# Sheet2.net
KiCad netlist of a schematic drawn in Altium Designer
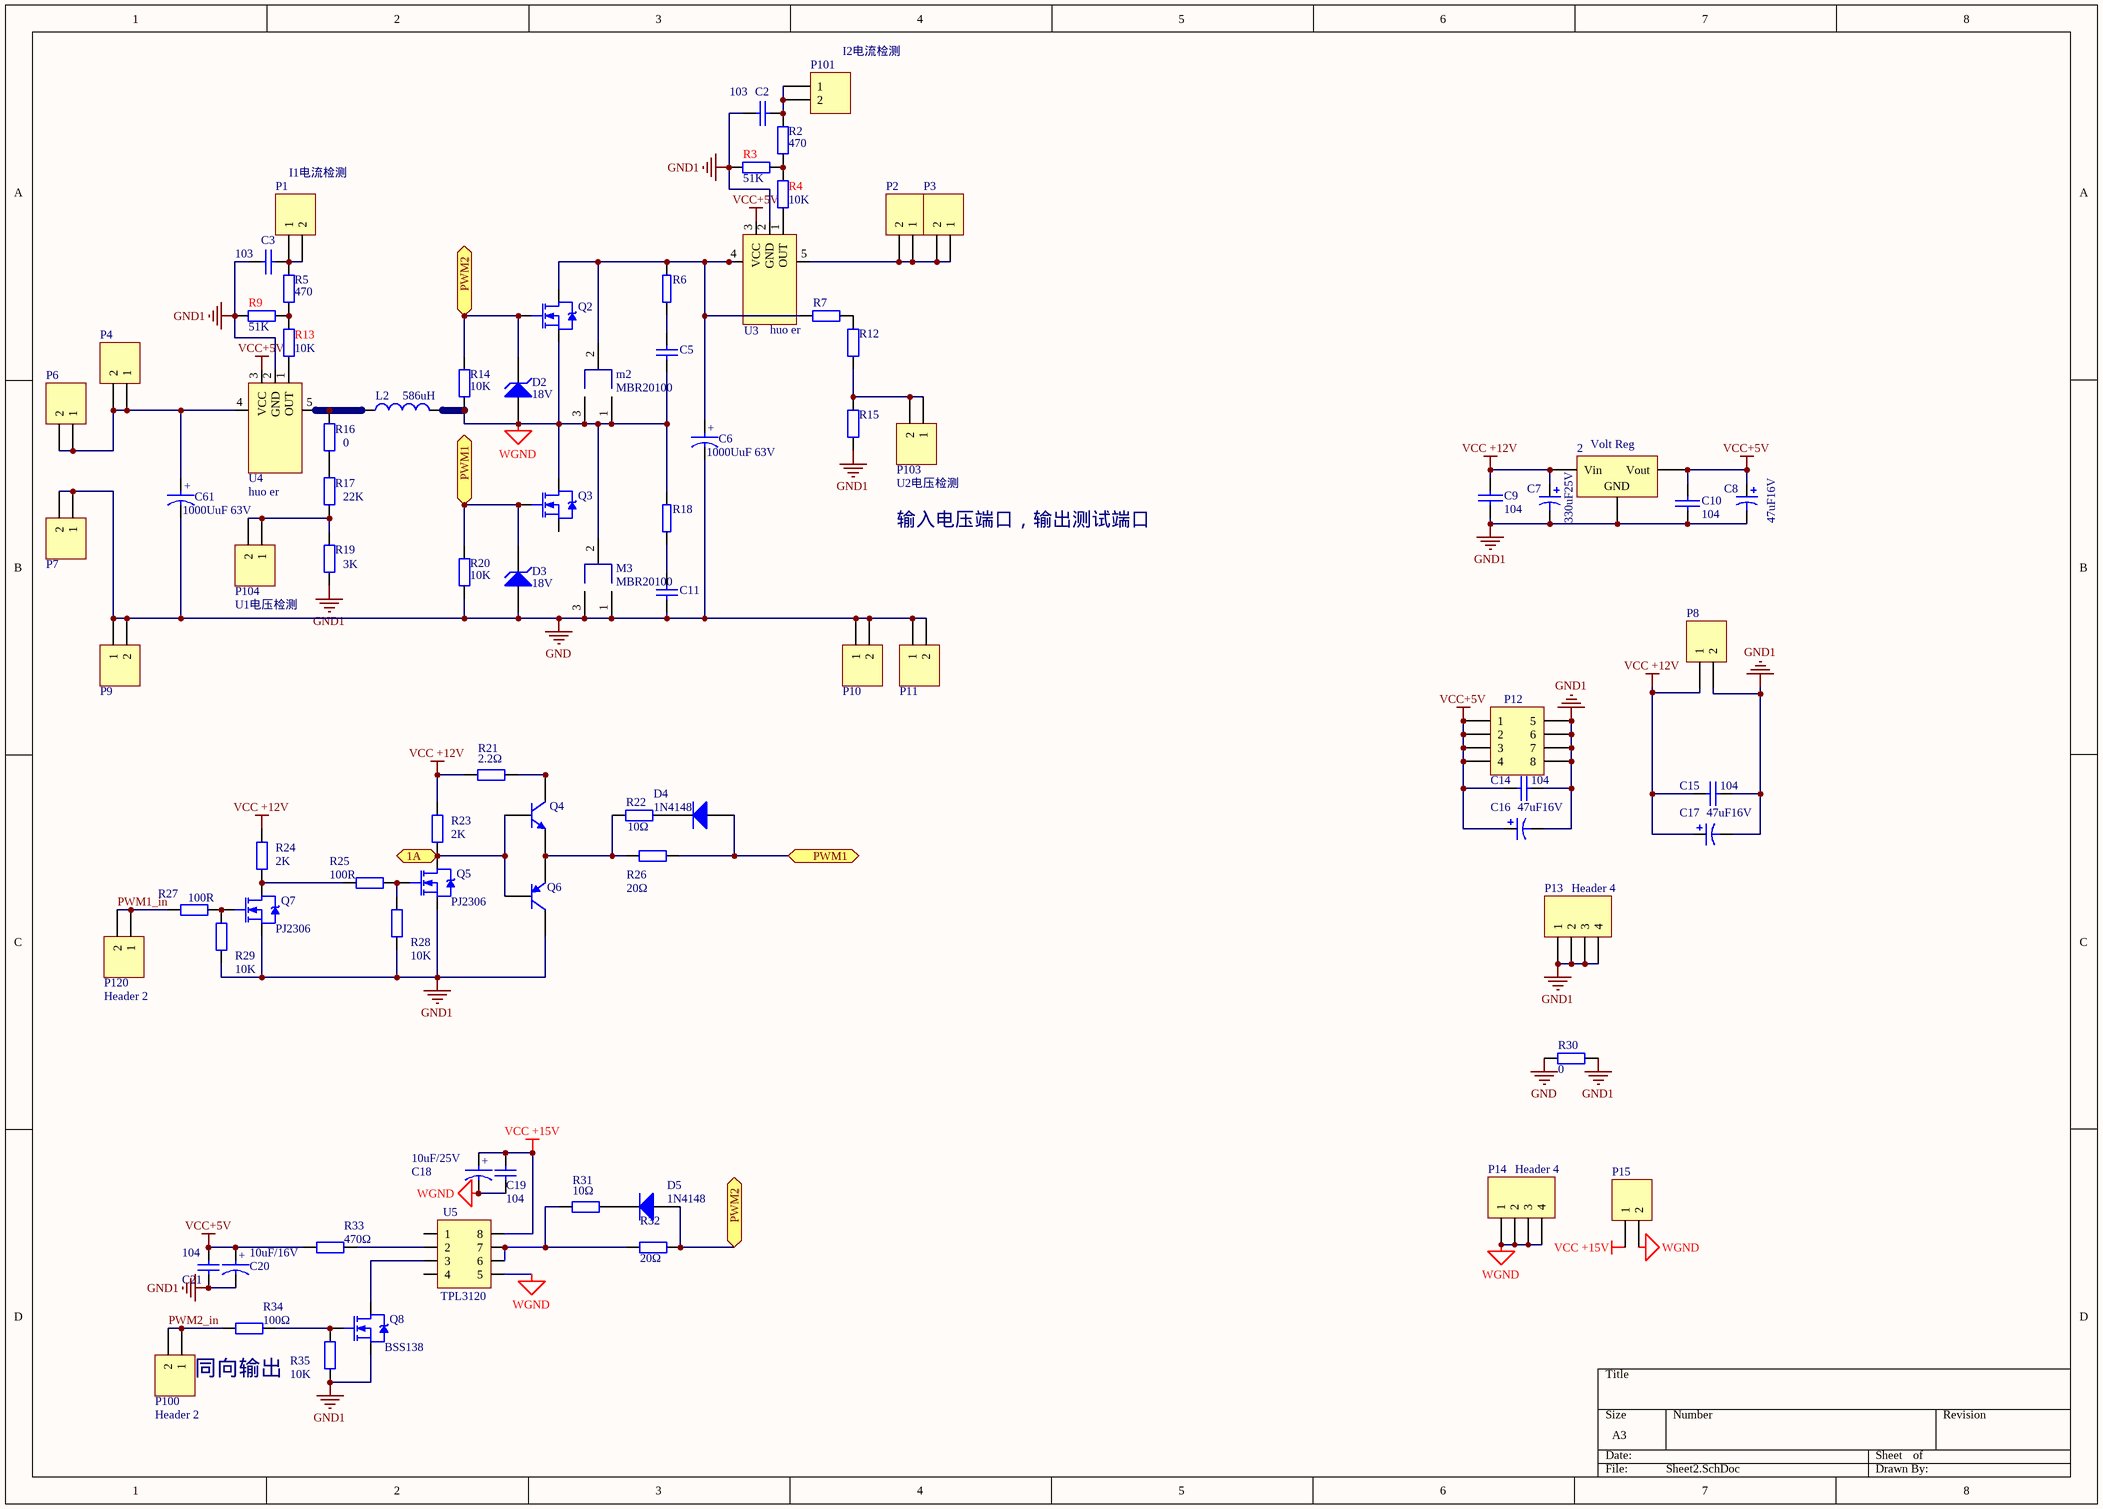
[diagram p0: Sheet2.SchDoc]

(export (version "E")
  (design (tool "Eeschema 10.0.6"))
  (components
    (comp (ref "2")
      (value "Volt Reg")
      (footprint "7812")
      (description "Voltage Regulator")
      (fields (field (name "PUBLISHER") "Altium Limited"))
      (libsource (lib "Miscellaneous Devices") (part "Volt Reg"))
    )
    (comp (ref "C2")
      (value "103")
      (footprint "C0805")
      (description "Capacitor")
      (libsource (lib "*") (part "CAP"))
    )
    (comp (ref "C3")
      (value "103")
      (footprint "C0805")
      (description "Capacitor")
      (libsource (lib "*") (part "CAP"))
    )
    (comp (ref "C5")
      (value "681")
      (footprint "接线端子")
      (description "Capacitor")
      (fields
        (field (name "MANUFACTURER") "Generic Components")
        (field (name "PUBLISHER") "Altium Hobart Technology Centre")
      )
      (libsource (lib "Miscellaneous Devices") (part "Cap"))
    )
    (comp (ref "C6")
      (value "1000UuF 63V")
      (footprint "RB.4/.8")
      (description "Capacitor")
      (libsource (lib "*") (part "CAPACITOR POL"))
    )
    (comp (ref "C7")
      (value "330uF25V")
      (footprint "RB.2/.4_1")
      (description "Polarized Capacitor (Radial)")
      (fields (field (name "PUBLISHER") "Altium Limited"))
      (libsource (lib "Miscellaneous Devices") (part "Cap Pol1"))
    )
    (comp (ref "C8")
      (value "47uF16V")
      (footprint "RB.1/.2")
      (description "Polarized Capacitor (Radial)")
      (fields (field (name "PUBLISHER") "Altium Limited"))
      (libsource (lib "Miscellaneous Devices") (part "Cap Pol1"))
    )
    (comp (ref "C9")
      (value "104")
      (footprint "C0805")
      (description "Capacitor")
      (libsource (lib "*") (part "CAP"))
    )
    (comp (ref "C10")
      (value "104")
      (footprint "C0805")
      (description "Capacitor")
      (libsource (lib "*") (part "CAP"))
    )
    (comp (ref "C11")
      (value "681")
      (footprint "接线端子")
      (description "Capacitor")
      (fields
        (field (name "MANUFACTURER") "Generic Components")
        (field (name "PUBLISHER") "Altium Hobart Technology Centre")
      )
      (libsource (lib "Miscellaneous Devices") (part "Cap"))
    )
    (comp (ref "C14")
      (value "104")
      (footprint "C0805")
      (description "Capacitor")
      (libsource (lib "*") (part "CAP"))
    )
    (comp (ref "C15")
      (value "104")
      (footprint "C0805")
      (description "Capacitor")
      (libsource (lib "*") (part "CAP"))
    )
    (comp (ref "C16")
      (value "47uF16V")
      (footprint "RB.1/.2")
      (description "Polarized Capacitor (Radial)")
      (fields (field (name "PUBLISHER") "Altium Limited"))
      (libsource (lib "Miscellaneous Devices") (part "Cap Pol1"))
    )
    (comp (ref "C17")
      (value "47uF16V")
      (footprint "RB.1/.2")
      (description "Polarized Capacitor (Radial)")
      (fields (field (name "PUBLISHER") "Altium Limited"))
      (libsource (lib "Miscellaneous Devices") (part "Cap Pol1"))
    )
    (comp (ref "C18")
      (value "10uF/25V")
      (footprint "RB.1/.2")
      (description "Capacitor")
      (libsource (lib "*") (part "CAPACITOR POL"))
    )
    (comp (ref "C19")
      (value "104")
      (footprint "C0805")
      (description "Capacitor")
      (fields
        (field (name "MANUFACTURER") "Generic Components")
        (field (name "PUBLISHER") "Altium Hobart Technology Centre")
      )
      (libsource (lib "Miscellaneous Devices") (part "Cap"))
    )
    (comp (ref "C20")
      (value "10uF/16V")
      (footprint "RB.1/.2")
      (description "Capacitor")
      (libsource (lib "*") (part "CAPACITOR POL"))
    )
    (comp (ref "C21")
      (value "104")
      (footprint "C0805")
      (description "Capacitor")
      (fields
        (field (name "MANUFACTURER") "Generic Components")
        (field (name "PUBLISHER") "Altium Hobart Technology Centre")
      )
      (libsource (lib "Miscellaneous Devices") (part "Cap"))
    )
    (comp (ref "C61")
      (value "1000UuF 63V")
      (footprint "RB.4/.8")
      (description "Capacitor")
      (libsource (lib "*") (part "CAPACITOR POL"))
    )
    (comp (ref "D2")
      (value "D Zener")
      (footprint "DIODE0.4_ZD")
      (description "Zener Diode")
      (fields
        (field (name "MANUFACTURER") "Generic Components")
        (field (name "SUBCLASS") "18V")
        (field (name "PUBLISHER") "Altium Hobart Technology Centre")
      )
      (libsource (lib "Miscellaneous Devices") (part "D Zener"))
    )
    (comp (ref "D3")
      (value "D Zener")
      (footprint "DIODE0.4_ZD")
      (description "Zener Diode")
      (fields
        (field (name "MANUFACTURER") "Generic Components")
        (field (name "SUBCLASS") "18V")
        (field (name "PUBLISHER") "Altium Hobart Technology Centre")
      )
      (libsource (lib "Miscellaneous Devices") (part "D Zener"))
    )
    (comp (ref "D4")
      (value "1N4148")
      (footprint "1206d")
      (description "Default Diode")
      (fields
        (field (name "MANUFACTURER") "Generic Components")
        (field (name "PUBLISHER") "Altium Hobart Technology Centre")
      )
      (libsource (lib "Miscellaneous Devices") (part "Diode"))
    )
    (comp (ref "D5")
      (value "1N4148")
      (footprint "1206d")
      (description "Default Diode")
      (fields
        (field (name "MANUFACTURER") "Generic Components")
        (field (name "PUBLISHER") "Altium Hobart Technology Centre")
      )
      (libsource (lib "Miscellaneous Devices") (part "Diode"))
    )
    (comp (ref "L2")
      (value "586uH")
      (footprint "130060")
      (description "Inductor")
      (fields (field (name "Comment") "12uH") (field (name "PUBLISHER") "Altium Limited"))
      (libsource (lib "older_ad09原理图") (part "Inductor_2"))
    )
    (comp (ref "m2") (value "MBR20100") (footprint "SFM-T3/A4.7V") (libsource (lib "Schlib1") (part "20010")))
    (comp (ref "M3") (value "MBR20100") (footprint "SFM-T3/A4.7V") (libsource (lib "Schlib1") (part "20010")))
    (comp (ref "P1")
      (value "I1电流检测")
      (footprint "HDR1X2")
      (description "Header, 2-Pin")
      (fields (field (name "PUBLISHER") "Altium Limited"))
      (libsource (lib "") (part "Header 2_2"))
    )
    (comp (ref "P2")
      (value "Header 2")
      (footprint "冷压插头")
      (description "Header, 2-Pin")
      (fields (field (name "PUBLISHER") "Altium Limited"))
      (libsource (lib "") (part "Header 2_1"))
    )
    (comp (ref "P3")
      (value "Header 2")
      (footprint "冷压插头")
      (description "Header, 2-Pin")
      (fields (field (name "PUBLISHER") "Altium Limited"))
      (libsource (lib "") (part "Header 2_1"))
    )
    (comp (ref "P4")
      (value "Header 2")
      (footprint "冷压插头")
      (description "Header, 2-Pin")
      (fields (field (name "PUBLISHER") "Altium Limited"))
      (libsource (lib "") (part "Header 2_1"))
    )
    (comp (ref "P6")
      (value "Header 2")
      (footprint "冷压插头")
      (description "Header, 2-Pin")
      (fields (field (name "PUBLISHER") "Altium Limited"))
      (libsource (lib "") (part "Header 2_1"))
    )
    (comp (ref "P7")
      (value "Header 2")
      (footprint "冷压插头")
      (description "Header, 2-Pin")
      (fields (field (name "PUBLISHER") "Altium Limited"))
      (libsource (lib "Miscellaneous Connectors") (part "Header 2"))
    )
    (comp (ref "P8")
      (value "Header 2")
      (footprint "SIP2_B")
      (description "Header, 2-Pin")
      (fields (field (name "PUBLISHER") "Altium Limited"))
      (libsource (lib "") (part "Header 2_2"))
    )
    (comp (ref "P9")
      (value "Header 2")
      (footprint "冷压插头")
      (description "Header, 2-Pin")
      (fields (field (name "PUBLISHER") "Altium Limited"))
      (libsource (lib "") (part "Header 2_3"))
    )
    (comp (ref "P10")
      (value "Header 2")
      (footprint "冷压插头")
      (description "Header, 2-Pin")
      (fields (field (name "PUBLISHER") "Altium Limited"))
      (libsource (lib "") (part "Header 2_3"))
    )
    (comp (ref "P11")
      (value "Header 2")
      (footprint "冷压插头")
      (description "Header, 2-Pin")
      (fields (field (name "PUBLISHER") "Altium Limited"))
      (libsource (lib "") (part "Header 2_3"))
    )
    (comp (ref "P12")
      (value "~")
      (footprint "HDR2X4_CEN")
      (description "Header, 4-Pin, Dual row")
      (fields (field (name "PUBLISHER") "Altium Limited"))
      (libsource (lib "Miscellaneous Connectors") (part "Header 4X2A"))
    )
    (comp (ref "P13")
      (value "Header 4")
      (footprint "HDR1X4")
      (description "Header, 4-Pin")
      (fields (field (name "PUBLISHER") "Altium Limited"))
      (libsource (lib "Miscellaneous Connectors") (part "Header 4"))
    )
    (comp (ref "P14")
      (value "Header 4")
      (footprint "HDR1X4")
      (description "Header, 4-Pin")
      (fields (field (name "PUBLISHER") "Altium Limited"))
      (libsource (lib "Miscellaneous Connectors") (part "Header 4"))
    )
    (comp (ref "P15")
      (value "Header 2")
      (footprint "SIP2_B")
      (description "Header, 2-Pin")
      (fields (field (name "PUBLISHER") "Altium Limited"))
      (libsource (lib "") (part "Header 2_2"))
    )
    (comp (ref "P100")
      (value "Header 2")
      (footprint "HDR1X2")
      (description "Header, 2-Pin")
      (fields (field (name "PUBLISHER") "Altium Limited"))
      (libsource (lib "Miscellaneous Connectors") (part "Header 2"))
    )
    (comp (ref "P101")
      (value "I2电流检测")
      (footprint "HDR1X2")
      (description "Header, 2-Pin")
      (fields (field (name "PUBLISHER") "Altium Limited"))
      (libsource (lib "") (part "Header 2_4"))
    )
    (comp (ref "P103")
      (value "U2电压检测")
      (footprint "HDR1X2")
      (description "Header, 2-Pin")
      (fields (field (name "PUBLISHER") "Altium Limited"))
      (libsource (lib "Miscellaneous Connectors") (part "Header 2"))
    )
    (comp (ref "P104")
      (value "U1电压检测")
      (footprint "HDR1X2")
      (description "Header, 2-Pin")
      (fields (field (name "PUBLISHER") "Altium Limited"))
      (libsource (lib "Miscellaneous Connectors") (part "Header 2"))
    )
    (comp (ref "P120")
      (value "Header 2")
      (footprint "HDR1X2")
      (description "Header, 2-Pin")
      (fields (field (name "PUBLISHER") "Altium Limited"))
      (libsource (lib "Miscellaneous Connectors") (part "Header 2"))
    )
    (comp (ref "Q2")
      (value "IRF830")
      (footprint "SFM-T3/A4.7V")
      (description "CQ-IRF840")
      (libsource (lib "*") (part "IRF840"))
    )
    (comp (ref "Q3")
      (value "IRF830")
      (footprint "SFM-T3/A4.7V")
      (description "CQ-IRF840")
      (libsource (lib "*") (part "IRF840"))
    )
    (comp (ref "Q4")
      (value "8050")
      (footprint "TO-92")
      (description "NPN General Purpose Amplifier")
      (fields
        (field (name "MANUFACTURER") "Generic Components")
        (field (name "PUBLISHER") "Altium Hobart Technology Centre")
      )
      (libsource (lib "Miscellaneous Devices") (part "2N3904"))
    )
    (comp (ref "Q5")
      (value "PJ2306")
      (footprint "sot-23")
      (description "CQ-IRF840")
      (libsource (lib "") (part "IRF840_1"))
    )
    (comp (ref "Q6")
      (value "8550")
      (footprint "TO-92")
      (description "PNP Bipolar Transistor")
      (fields
        (field (name "MANUFACTURER") "Generic Components")
        (field (name "PUBLISHER") "Altium Hobart Technology Centre")
      )
      (libsource (lib "Miscellaneous Devices") (part "PNP"))
    )
    (comp (ref "Q7")
      (value "PJ2306")
      (footprint "sot-23")
      (description "CQ-IRF840")
      (libsource (lib "") (part "IRF840_1"))
    )
    (comp (ref "Q8")
      (value "BSS138")
      (footprint "sot-23")
      (description "CQ-IRF840")
      (libsource (lib "") (part "IRF840_1"))
    )
    (comp (ref "R2")
      (value "470")
      (footprint "R0805")
      (description "Resistor")
      (fields
        (field (name "MANUFACTURER") "Generic Components")
        (field (name "Comment") "Res2")
        (field (name "PUBLISHER") "Altium Hobart Technology Centre")
      )
      (libsource (lib "") (part "Res2_1"))
    )
    (comp (ref "R3")
      (value "51K")
      (footprint "R0805")
      (description "Resistor")
      (fields (field (name "PUBLISHER") "Altium Limited"))
      (libsource (lib "") (part "Res2_2"))
    )
    (comp (ref "R4")
      (value "10K")
      (footprint "R0805")
      (description "Resistor")
      (fields (field (name "PUBLISHER") "Altium Limited"))
      (libsource (lib "") (part "Res2_3"))
    )
    (comp (ref "R5")
      (value "470")
      (footprint "R0805")
      (description "Resistor")
      (fields
        (field (name "MANUFACTURER") "Generic Components")
        (field (name "Comment") "Res2")
        (field (name "PUBLISHER") "Altium Hobart Technology Centre")
      )
      (libsource (lib "") (part "Res2_1"))
    )
    (comp (ref "R6") (value "20Ω/2W") (footprint "S-R2W") (libsource (lib "*") (part "R")))
    (comp (ref "R7")
      (value "Res2")
      (footprint "R0805")
      (description "Resistor")
      (fields
        (field (name "MANUFACTURER") "Generic Components")
        (field (name "PUBLISHER") "Altium Hobart Technology Centre")
      )
      (libsource (lib "Miscellaneous Devices") (part "Res2"))
    )
    (comp (ref "R9")
      (value "51K")
      (footprint "R0805")
      (description "Resistor")
      (fields (field (name "PUBLISHER") "Altium Limited"))
      (libsource (lib "") (part "Res2_2"))
    )
    (comp (ref "R12")
      (value "Res2")
      (footprint "R0805")
      (description "Resistor")
      (fields
        (field (name "MANUFACTURER") "Generic Components")
        (field (name "PUBLISHER") "Altium Hobart Technology Centre")
      )
      (libsource (lib "") (part "Res2_1"))
    )
    (comp (ref "R13")
      (value "10K")
      (footprint "R0805")
      (description "Resistor")
      (fields (field (name "PUBLISHER") "Altium Limited"))
      (libsource (lib "") (part "Res2_3"))
    )
    (comp (ref "R14")
      (value "10K")
      (footprint "R0805")
      (description "Resistor")
      (fields
        (field (name "MANUFACTURER") "Generic Components")
        (field (name "Comment") "Res2")
        (field (name "PUBLISHER") "Altium Hobart Technology Centre")
      )
      (libsource (lib "") (part "Res2_1"))
    )
    (comp (ref "R15")
      (value "Res2")
      (footprint "R0805")
      (description "Resistor")
      (fields
        (field (name "MANUFACTURER") "Generic Components")
        (field (name "PUBLISHER") "Altium Hobart Technology Centre")
      )
      (libsource (lib "") (part "Res2_1"))
    )
    (comp (ref "R16")
      (value "0")
      (footprint "R0805")
      (description "Resistor")
      (fields
        (field (name "MANUFACTURER") "Generic Components")
        (field (name "PUBLISHER") "Altium Hobart Technology Centre")
      )
      (libsource (lib "") (part "Res2_1"))
    )
    (comp (ref "R17")
      (value "22K")
      (footprint "R0805")
      (description "Resistor")
      (fields
        (field (name "MANUFACTURER") "Generic Components")
        (field (name "PUBLISHER") "Altium Hobart Technology Centre")
      )
      (libsource (lib "") (part "Res2_1"))
    )
    (comp (ref "R18") (value "20Ω/2W") (footprint "S-R2W") (libsource (lib "*") (part "R")))
    (comp (ref "R19")
      (value "3K")
      (footprint "R0805")
      (description "Resistor")
      (fields
        (field (name "MANUFACTURER") "Generic Components")
        (field (name "PUBLISHER") "Altium Hobart Technology Centre")
      )
      (libsource (lib "") (part "Res2_1"))
    )
    (comp (ref "R20")
      (value "10K")
      (footprint "R0805")
      (description "Resistor")
      (fields
        (field (name "MANUFACTURER") "Generic Components")
        (field (name "Comment") "Res2")
        (field (name "PUBLISHER") "Altium Hobart Technology Centre")
      )
      (libsource (lib "") (part "Res2_1"))
    )
    (comp (ref "R21")
      (value "2.2Ω")
      (footprint "R0805")
      (description "Resistor")
      (fields
        (field (name "MANUFACTURER") "Generic Components")
        (field (name "Comment") "Res2")
        (field (name "PUBLISHER") "Altium Hobart Technology Centre")
      )
      (libsource (lib "") (part "Res2_2"))
    )
    (comp (ref "R22")
      (value "10Ω")
      (footprint "R0805")
      (description "Resistor")
      (fields
        (field (name "MANUFACTURER") "Generic Components")
        (field (name "PUBLISHER") "Altium Hobart Technology Centre")
      )
      (libsource (lib "") (part "Res2_2"))
    )
    (comp (ref "R23")
      (value "2K")
      (footprint "R0805")
      (description "Resistor")
      (fields
        (field (name "MANUFACTURER") "Generic Components")
        (field (name "Comment") "Res2")
        (field (name "PUBLISHER") "Altium Hobart Technology Centre")
      )
      (libsource (lib "") (part "Res2_1"))
    )
    (comp (ref "R24")
      (value "2K")
      (footprint "R0805")
      (description "Resistor")
      (fields
        (field (name "MANUFACTURER") "Generic Components")
        (field (name "Comment") "Res2")
        (field (name "PUBLISHER") "Altium Hobart Technology Centre")
      )
      (libsource (lib "") (part "Res2_1"))
    )
    (comp (ref "R25")
      (value "100R")
      (footprint "R0805")
      (description "Resistor")
      (fields
        (field (name "MANUFACTURER") "Generic Components")
        (field (name "PUBLISHER") "Altium Hobart Technology Centre")
      )
      (libsource (lib "Miscellaneous Devices") (part "Res2"))
    )
    (comp (ref "R26")
      (value "20Ω")
      (footprint "R0805")
      (description "Resistor")
      (fields
        (field (name "MANUFACTURER") "Generic Components")
        (field (name "PUBLISHER") "Altium Hobart Technology Centre")
      )
      (libsource (lib "") (part "Res2_2"))
    )
    (comp (ref "R27")
      (value "100R")
      (footprint "R0805")
      (description "Resistor")
      (fields
        (field (name "MANUFACTURER") "Generic Components")
        (field (name "PUBLISHER") "Altium Hobart Technology Centre")
      )
      (libsource (lib "Miscellaneous Devices") (part "Res2"))
    )
    (comp (ref "R28")
      (value "10K")
      (footprint "R0805")
      (description "Resistor")
      (fields
        (field (name "MANUFACTURER") "Generic Components")
        (field (name "Comment") "Res2")
        (field (name "PUBLISHER") "Altium Hobart Technology Centre")
      )
      (libsource (lib "") (part "Res2_1"))
    )
    (comp (ref "R29")
      (value "10K")
      (footprint "R0805")
      (description "Resistor")
      (fields
        (field (name "MANUFACTURER") "Generic Components")
        (field (name "Comment") "Res2")
        (field (name "PUBLISHER") "Altium Hobart Technology Centre")
      )
      (libsource (lib "") (part "Res2_1"))
    )
    (comp (ref "R30")
      (value "0")
      (footprint "R0805")
      (description "Resistor")
      (fields (field (name "Comment") "Res2") (field (name "PUBLISHER") "Altium Limited"))
      (libsource (lib "") (part "Res2_2"))
    )
    (comp (ref "R31")
      (value "10Ω")
      (footprint "R0805")
      (description "Resistor")
      (fields
        (field (name "MANUFACTURER") "Generic Components")
        (field (name "Comment") "Res2")
        (field (name "PUBLISHER") "Altium Hobart Technology Centre")
      )
      (libsource (lib "") (part "Res2_2"))
    )
    (comp (ref "R32")
      (value "20Ω")
      (footprint "R0805")
      (description "Resistor")
      (fields
        (field (name "MANUFACTURER") "Generic Components")
        (field (name "PUBLISHER") "Altium Hobart Technology Centre")
      )
      (libsource (lib "") (part "Res2_2"))
    )
    (comp (ref "R33")
      (value "470Ω")
      (footprint "R0805")
      (description "Resistor")
      (fields
        (field (name "MANUFACTURER") "Generic Components")
        (field (name "PUBLISHER") "Altium Hobart Technology Centre")
      )
      (libsource (lib "") (part "Res2_2"))
    )
    (comp (ref "R34")
      (value "100Ω")
      (footprint "R0805")
      (description "Resistor")
      (fields
        (field (name "MANUFACTURER") "Generic Components")
        (field (name "PUBLISHER") "Altium Hobart Technology Centre")
      )
      (libsource (lib "") (part "Res2_2"))
    )
    (comp (ref "R35")
      (value "10K")
      (footprint "R0805")
      (description "Resistor")
      (fields
        (field (name "MANUFACTURER") "Generic Components")
        (field (name "Comment") "Res2")
        (field (name "PUBLISHER") "Altium Hobart Technology Centre")
      )
      (libsource (lib "") (part "Res2_1"))
    )
    (comp (ref "U3") (value "huo er") (footprint "霍尔传感器-40A") (libsource (lib "LM358") (part "HOUER")))
    (comp (ref "U4") (value "huo er") (footprint "霍尔传感器-40A") (libsource (lib "LM358") (part "HOUER")))
    (comp (ref "U5") (value "TPL3120") (footprint "DIP-8") (libsource (lib "*") (part "LM386")))
  )
  (nets
    (net (code "1") (name "/1A") (class "Default")
      (node (ref "Q4") (pin "1") (pinfunction "B_1") (pintype "passive"))
      (node (ref "Q5") (pin "3") (pinfunction "3_3") (pintype "passive"))
      (node (ref "Q6") (pin "2") (pinfunction "B_2") (pintype "passive"))
      (node (ref "R23") (pin "1") (pinfunction "1_1") (pintype "passive"))
    )
    (net (code "2") (name "/PWM1") (class "Default")
      (node (ref "D3") (pin "2") (pinfunction "2_2") (pintype "passive"))
      (node (ref "D4") (pin "1") (pinfunction "1_1") (pintype "passive"))
      (node (ref "Q3") (pin "1") (pinfunction "1_1") (pintype "passive"))
      (node (ref "R20") (pin "2") (pinfunction "2_2") (pintype "passive"))
      (node (ref "R26") (pin "2") (pinfunction "2_2") (pintype "passive"))
    )
    (net (code "3") (name "/PWM1_in") (class "Default")
      (node (ref "P120") (pin "1") (pinfunction "1_1") (pintype "passive"))
      (node (ref "P120") (pin "2") (pinfunction "2_2") (pintype "passive"))
      (node (ref "R27") (pin "2") (pinfunction "2_2") (pintype "passive"))
    )
    (net (code "4") (name "/PWM2") (class "Default")
      (node (ref "D2") (pin "2") (pinfunction "2_2") (pintype "passive"))
      (node (ref "D5") (pin "1") (pinfunction "1_1") (pintype "passive"))
      (node (ref "Q2") (pin "1") (pinfunction "1_1") (pintype "passive"))
      (node (ref "R14") (pin "2") (pinfunction "2_2") (pintype "passive"))
      (node (ref "R32") (pin "2") (pinfunction "2_2") (pintype "passive"))
    )
    (net (code "5") (name "/PWM2_in") (class "Default")
      (node (ref "P100") (pin "1") (pinfunction "1_1") (pintype "passive"))
      (node (ref "P100") (pin "2") (pinfunction "2_2") (pintype "passive"))
      (node (ref "R34") (pin "1") (pinfunction "1_1") (pintype "passive"))
    )
    (net (code "6") (name "GND") (class "Default")
      (node (ref "C11") (pin "2") (pinfunction "2_2") (pintype "passive"))
      (node (ref "C6") (pin "2") (pinfunction "2_2") (pintype "passive"))
      (node (ref "C61") (pin "2") (pinfunction "2_2") (pintype "passive"))
      (node (ref "D3") (pin "1") (pinfunction "1_1") (pintype "passive"))
      (node (ref "M3") (pin "1") (pinfunction "1_1") (pintype "passive"))
      (node (ref "M3") (pin "3") (pinfunction "3_3") (pintype "passive"))
      (node (ref "P10") (pin "1") (pinfunction "1_1") (pintype "passive"))
      (node (ref "P10") (pin "2") (pinfunction "2_2") (pintype "passive"))
      (node (ref "P11") (pin "1") (pinfunction "1_1") (pintype "passive"))
      (node (ref "P11") (pin "2") (pinfunction "2_2") (pintype "passive"))
      (node (ref "P7") (pin "1") (pinfunction "1_1") (pintype "passive"))
      (node (ref "P7") (pin "2") (pinfunction "2_2") (pintype "passive"))
      (node (ref "P9") (pin "1") (pinfunction "1_1") (pintype "passive"))
      (node (ref "P9") (pin "2") (pinfunction "2_2") (pintype "passive"))
      (node (ref "R20") (pin "1") (pinfunction "1_1") (pintype "passive"))
      (node (ref "R30") (pin "1") (pinfunction "1_1") (pintype "passive"))
    )
    (net (code "7") (name "GND1") (class "Default")
      (node (ref "2") (pin "2") (pinfunction "GND_2") (pintype "passive"))
      (node (ref "C10") (pin "1") (pinfunction "1_1") (pintype "passive"))
      (node (ref "C14") (pin "1") (pinfunction "1_1") (pintype "passive"))
      (node (ref "C15") (pin "1") (pinfunction "1_1") (pintype "passive"))
      (node (ref "C16") (pin "2") (pinfunction "2_2") (pintype "passive"))
      (node (ref "C17") (pin "2") (pinfunction "2_2") (pintype "passive"))
      (node (ref "C2") (pin "2") (pinfunction "2_2") (pintype "passive"))
      (node (ref "C20") (pin "2") (pinfunction "2_2") (pintype "passive"))
      (node (ref "C21") (pin "2") (pinfunction "2_2") (pintype "passive"))
      (node (ref "C3") (pin "2") (pinfunction "2_2") (pintype "passive"))
      (node (ref "C7") (pin "2") (pinfunction "2_2") (pintype "passive"))
      (node (ref "C8") (pin "2") (pinfunction "2_2") (pintype "passive"))
      (node (ref "C9") (pin "1") (pinfunction "1_1") (pintype "passive"))
      (node (ref "P12") (pin "5") (pinfunction "5_5") (pintype "passive"))
      (node (ref "P12") (pin "6") (pinfunction "6_6") (pintype "passive"))
      (node (ref "P12") (pin "7") (pinfunction "7_7") (pintype "passive"))
      (node (ref "P12") (pin "8") (pinfunction "8_8") (pintype "passive"))
      (node (ref "P13") (pin "1") (pinfunction "1_1") (pintype "passive"))
      (node (ref "P13") (pin "2") (pinfunction "2_2") (pintype "passive"))
      (node (ref "P13") (pin "3") (pinfunction "3_3") (pintype "passive"))
      (node (ref "P13") (pin "4") (pinfunction "4_4") (pintype "passive"))
      (node (ref "P8") (pin "2") (pinfunction "2_2") (pintype "passive"))
      (node (ref "Q5") (pin "2") (pinfunction "2_2") (pintype "passive"))
      (node (ref "Q6") (pin "3") (pinfunction "C_3") (pintype "passive"))
      (node (ref "Q7") (pin "2") (pinfunction "2_2") (pintype "passive"))
      (node (ref "Q8") (pin "2") (pinfunction "2_2") (pintype "passive"))
      (node (ref "R15") (pin "1") (pinfunction "1_1") (pintype "passive"))
      (node (ref "R19") (pin "1") (pinfunction "1_1") (pintype "passive"))
      (node (ref "R28") (pin "1") (pinfunction "1_1") (pintype "passive"))
      (node (ref "R29") (pin "1") (pinfunction "1_1") (pintype "passive"))
      (node (ref "R3") (pin "1") (pinfunction "1_1") (pintype "passive"))
      (node (ref "R30") (pin "2") (pinfunction "2_2") (pintype "passive"))
      (node (ref "R35") (pin "1") (pinfunction "1_1") (pintype "passive"))
      (node (ref "R9") (pin "1") (pinfunction "1_1") (pintype "passive"))
      (node (ref "U3") (pin "2") (pinfunction "GND_2") (pintype "power_in"))
      (node (ref "U4") (pin "2") (pinfunction "GND_2") (pintype "power_in"))
    )
    (net (code "8") (name "Net-(C2-Pad1)") (class "Default")
      (node (ref "C2") (pin "1") (pinfunction "1_1") (pintype "passive"))
      (node (ref "P101") (pin "1") (pinfunction "1_1") (pintype "passive"))
      (node (ref "P101") (pin "2") (pinfunction "2_2") (pintype "passive"))
      (node (ref "R2") (pin "2") (pinfunction "2_2") (pintype "passive"))
    )
    (net (code "9") (name "Net-(C3-Pad1)") (class "Default")
      (node (ref "C3") (pin "1") (pinfunction "1_1") (pintype "passive"))
      (node (ref "P1") (pin "1") (pinfunction "1_1") (pintype "passive"))
      (node (ref "P1") (pin "2") (pinfunction "2_2") (pintype "passive"))
      (node (ref "R5") (pin "2") (pinfunction "2_2") (pintype "passive"))
    )
    (net (code "10") (name "Net-(C5-Pad1)") (class "Default")
      (node (ref "C5") (pin "1") (pinfunction "1_1") (pintype "passive"))
      (node (ref "R6") (pin "2") (pinfunction "2_2") (pintype "passive"))
    )
    (net (code "11") (name "Net-(C6-Pad1)") (class "Default")
      (node (ref "C6") (pin "1") (pinfunction "1_1") (pintype "passive"))
      (node (ref "Q2") (pin "2") (pinfunction "2_2") (pintype "passive"))
      (node (ref "R6") (pin "1") (pinfunction "1_1") (pintype "passive"))
      (node (ref "R7") (pin "2") (pinfunction "2_2") (pintype "passive"))
      (node (ref "U3") (pin "4") (pintype "power_in"))
      (node (ref "m2") (pin "2") (pinfunction "2_2") (pintype "passive"))
    )
    (net (code "12") (name "Net-(C11-Pad1)") (class "Default")
      (node (ref "C11") (pin "1") (pinfunction "1_1") (pintype "passive"))
      (node (ref "R18") (pin "2") (pinfunction "2_2") (pintype "passive"))
    )
    (net (code "13") (name "Net-(C61-Pad1)") (class "Default")
      (node (ref "C61") (pin "1") (pinfunction "1_1") (pintype "passive"))
      (node (ref "P4") (pin "1") (pinfunction "1_1") (pintype "passive"))
      (node (ref "P4") (pin "2") (pinfunction "2_2") (pintype "passive"))
      (node (ref "P6") (pin "1") (pinfunction "1_1") (pintype "passive"))
      (node (ref "P6") (pin "2") (pinfunction "2_2") (pintype "passive"))
      (node (ref "U4") (pin "4") (pintype "power_in"))
    )
    (net (code "14") (name "Net-(D4-Pad2)") (class "Default")
      (node (ref "D4") (pin "2") (pinfunction "2_2") (pintype "passive"))
      (node (ref "R22") (pin "2") (pinfunction "2_2") (pintype "passive"))
    )
    (net (code "15") (name "Net-(D5-Pad2)") (class "Default")
      (node (ref "D5") (pin "2") (pinfunction "2_2") (pintype "passive"))
      (node (ref "R31") (pin "2") (pinfunction "2_2") (pintype "passive"))
    )
    (net (code "16") (name "Net-(L2-Pad1)") (class "Default")
      (node (ref "L2") (pin "1") (pinfunction "1_1") (pintype "passive"))
      (node (ref "R16") (pin "2") (pinfunction "2_2") (pintype "passive"))
      (node (ref "U4") (pin "5") (pintype "power_in"))
    )
    (net (code "17") (name "Net-(P2-Pad1)") (class "Default")
      (node (ref "P2") (pin "1") (pinfunction "1_1") (pintype "passive"))
      (node (ref "P2") (pin "2") (pinfunction "2_2") (pintype "passive"))
      (node (ref "P3") (pin "1") (pinfunction "1_1") (pintype "passive"))
      (node (ref "P3") (pin "2") (pinfunction "2_2") (pintype "passive"))
      (node (ref "U3") (pin "5") (pintype "power_in"))
    )
    (net (code "18") (name "Net-(P103-Pad1)") (class "Default")
      (node (ref "P103") (pin "1") (pinfunction "1_1") (pintype "passive"))
      (node (ref "P103") (pin "2") (pinfunction "2_2") (pintype "passive"))
      (node (ref "R12") (pin "1") (pinfunction "1_1") (pintype "passive"))
      (node (ref "R15") (pin "2") (pinfunction "2_2") (pintype "passive"))
    )
    (net (code "19") (name "Net-(P104-Pad1)") (class "Default")
      (node (ref "P104") (pin "1") (pinfunction "1_1") (pintype "passive"))
      (node (ref "P104") (pin "2") (pinfunction "2_2") (pintype "passive"))
      (node (ref "R17") (pin "1") (pinfunction "1_1") (pintype "passive"))
      (node (ref "R19") (pin "2") (pinfunction "2_2") (pintype "passive"))
    )
    (net (code "20") (name "Net-(Q4-C)") (class "Default")
      (node (ref "Q4") (pin "2") (pinfunction "C_2") (pintype "passive"))
      (node (ref "R21") (pin "2") (pinfunction "2_2") (pintype "passive"))
    )
    (net (code "21") (name "Net-(Q4-E)") (class "Default")
      (node (ref "Q4") (pin "3") (pinfunction "E_3") (pintype "passive"))
      (node (ref "Q6") (pin "1") (pinfunction "E_1") (pintype "passive"))
      (node (ref "R22") (pin "1") (pinfunction "1_1") (pintype "passive"))
      (node (ref "R26") (pin "1") (pinfunction "1_1") (pintype "passive"))
    )
    (net (code "22") (name "Net-(Q5-Pad1)") (class "Default")
      (node (ref "Q5") (pin "1") (pinfunction "1_1") (pintype "passive"))
      (node (ref "R25") (pin "1") (pinfunction "1_1") (pintype "passive"))
      (node (ref "R28") (pin "2") (pinfunction "2_2") (pintype "passive"))
    )
    (net (code "23") (name "Net-(Q7-Pad1)") (class "Default")
      (node (ref "Q7") (pin "1") (pinfunction "1_1") (pintype "passive"))
      (node (ref "R27") (pin "1") (pinfunction "1_1") (pintype "passive"))
      (node (ref "R29") (pin "2") (pinfunction "2_2") (pintype "passive"))
    )
    (net (code "24") (name "Net-(Q7-Pad3)") (class "Default")
      (node (ref "Q7") (pin "3") (pinfunction "3_3") (pintype "passive"))
      (node (ref "R24") (pin "1") (pinfunction "1_1") (pintype "passive"))
      (node (ref "R25") (pin "2") (pinfunction "2_2") (pintype "passive"))
    )
    (net (code "25") (name "Net-(Q8-Pad1)") (class "Default")
      (node (ref "Q8") (pin "1") (pinfunction "1_1") (pintype "passive"))
      (node (ref "R34") (pin "2") (pinfunction "2_2") (pintype "passive"))
      (node (ref "R35") (pin "2") (pinfunction "2_2") (pintype "passive"))
    )
    (net (code "26") (name "Net-(Q8-Pad3)") (class "Default")
      (node (ref "Q8") (pin "3") (pinfunction "3_3") (pintype "passive"))
      (node (ref "U5") (pin "3") (pinfunction "3_3") (pintype "passive"))
    )
    (net (code "27") (name "Net-(R2-Pad1)") (class "Default")
      (node (ref "R2") (pin "1") (pinfunction "1_1") (pintype "passive"))
      (node (ref "R3") (pin "2") (pinfunction "2_2") (pintype "passive"))
      (node (ref "R4") (pin "1") (pinfunction "1_1") (pintype "passive"))
    )
    (net (code "28") (name "Net-(R12-Pad2)") (class "Default")
      (node (ref "R12") (pin "2") (pinfunction "2_2") (pintype "passive"))
      (node (ref "R7") (pin "1") (pinfunction "1_1") (pintype "passive"))
    )
    (net (code "29") (name "Net-(R13-Pad1)") (class "Default")
      (node (ref "R13") (pin "1") (pinfunction "1_1") (pintype "passive"))
      (node (ref "R5") (pin "1") (pinfunction "1_1") (pintype "passive"))
      (node (ref "R9") (pin "2") (pinfunction "2_2") (pintype "passive"))
    )
    (net (code "30") (name "Net-(R16-Pad1)") (class "Default")
      (node (ref "R16") (pin "1") (pinfunction "1_1") (pintype "passive"))
      (node (ref "R17") (pin "2") (pinfunction "2_2") (pintype "passive"))
    )
    (net (code "31") (name "Net-(R31-Pad1)") (class "Default")
      (node (ref "R31") (pin "1") (pinfunction "1_1") (pintype "passive"))
      (node (ref "R32") (pin "1") (pinfunction "1_1") (pintype "passive"))
      (node (ref "U5") (pin "6") (pinfunction "6_6") (pintype "passive"))
      (node (ref "U5") (pin "7") (pinfunction "7_7") (pintype "passive"))
    )
    (net (code "32") (name "Net-(R33-Pad2)") (class "Default")
      (node (ref "R33") (pin "2") (pinfunction "2_2") (pintype "passive"))
      (node (ref "U5") (pin "2") (pinfunction "2_2") (pintype "passive"))
    )
    (net (code "33") (name "Net-(U3-OUT)") (class "Default")
      (node (ref "R4") (pin "2") (pinfunction "2_2") (pintype "passive"))
      (node (ref "U3") (pin "1") (pinfunction "OUT_1") (pintype "power_in"))
    )
    (net (code "34") (name "Net-(U4-OUT)") (class "Default")
      (node (ref "R13") (pin "2") (pinfunction "2_2") (pintype "passive"))
      (node (ref "U4") (pin "1") (pinfunction "OUT_1") (pintype "power_in"))
    )
    (net (code "35") (name "VCC +12V") (class "Default")
      (node (ref "2") (pin "1") (pinfunction "Vin_1") (pintype "passive"))
      (node (ref "C15") (pin "2") (pinfunction "2_2") (pintype "passive"))
      (node (ref "C17") (pin "1") (pinfunction "1_1") (pintype "passive"))
      (node (ref "C7") (pin "1") (pinfunction "1_1") (pintype "passive"))
      (node (ref "C9") (pin "2") (pinfunction "2_2") (pintype "passive"))
      (node (ref "P8") (pin "1") (pinfunction "1_1") (pintype "passive"))
      (node (ref "R21") (pin "1") (pinfunction "1_1") (pintype "passive"))
      (node (ref "R23") (pin "2") (pinfunction "2_2") (pintype "passive"))
      (node (ref "R24") (pin "2") (pinfunction "2_2") (pintype "passive"))
    )
    (net (code "36") (name "VCC +15V") (class "Default")
      (node (ref "C18") (pin "1") (pinfunction "1_1") (pintype "passive"))
      (node (ref "C19") (pin "1") (pinfunction "1_1") (pintype "passive"))
      (node (ref "P15") (pin "1") (pinfunction "1_1") (pintype "passive"))
      (node (ref "U5") (pin "8") (pinfunction "8_8") (pintype "passive"))
    )
    (net (code "37") (name "VCC+5V") (class "Default")
      (node (ref "2") (pin "3") (pinfunction "Vout_3") (pintype "passive"))
      (node (ref "C10") (pin "2") (pinfunction "2_2") (pintype "passive"))
      (node (ref "C14") (pin "2") (pinfunction "2_2") (pintype "passive"))
      (node (ref "C16") (pin "1") (pinfunction "1_1") (pintype "passive"))
      (node (ref "C20") (pin "1") (pinfunction "1_1") (pintype "passive"))
      (node (ref "C21") (pin "1") (pinfunction "1_1") (pintype "passive"))
      (node (ref "C8") (pin "1") (pinfunction "1_1") (pintype "passive"))
      (node (ref "P12") (pin "1") (pinfunction "1_1") (pintype "passive"))
      (node (ref "P12") (pin "2") (pinfunction "2_2") (pintype "passive"))
      (node (ref "P12") (pin "3") (pinfunction "3_3") (pintype "passive"))
      (node (ref "P12") (pin "4") (pinfunction "4_4") (pintype "passive"))
      (node (ref "R33") (pin "1") (pinfunction "1_1") (pintype "passive"))
      (node (ref "U3") (pin "3") (pinfunction "VCC_3") (pintype "power_in"))
      (node (ref "U4") (pin "3") (pinfunction "VCC_3") (pintype "power_in"))
    )
    (net (code "38") (name "WGND") (class "Default")
      (node (ref "C18") (pin "2") (pinfunction "2_2") (pintype "passive"))
      (node (ref "C19") (pin "2") (pinfunction "2_2") (pintype "passive"))
      (node (ref "C5") (pin "2") (pinfunction "2_2") (pintype "passive"))
      (node (ref "D2") (pin "1") (pinfunction "1_1") (pintype "passive"))
      (node (ref "L2") (pin "2") (pinfunction "2_2") (pintype "passive"))
      (node (ref "M3") (pin "2") (pinfunction "2_2") (pintype "passive"))
      (node (ref "P14") (pin "1") (pinfunction "1_1") (pintype "passive"))
      (node (ref "P14") (pin "2") (pinfunction "2_2") (pintype "passive"))
      (node (ref "P14") (pin "3") (pinfunction "3_3") (pintype "passive"))
      (node (ref "P14") (pin "4") (pinfunction "4_4") (pintype "passive"))
      (node (ref "P15") (pin "2") (pinfunction "2_2") (pintype "passive"))
      (node (ref "Q2") (pin "3") (pinfunction "3_3") (pintype "passive"))
      (node (ref "Q3") (pin "2") (pinfunction "2_2") (pintype "passive"))
      (node (ref "R14") (pin "1") (pinfunction "1_1") (pintype "passive"))
      (node (ref "R18") (pin "1") (pinfunction "1_1") (pintype "passive"))
      (node (ref "U5") (pin "5") (pinfunction "5_5") (pintype "passive"))
      (node (ref "m2") (pin "1") (pinfunction "1_1") (pintype "passive"))
      (node (ref "m2") (pin "3") (pinfunction "3_3") (pintype "passive"))
    )
    (net (code "39") (name "unconnected-(Q3-Pad3)") (class "Default")
      (node (ref "Q3") (pin "3") (pinfunction "3_3") (pintype "passive"))
    )
    (net (code "40") (name "unconnected-(U5-Pad1)") (class "Default")
      (node (ref "U5") (pin "1") (pinfunction "1_1") (pintype "passive"))
    )
    (net (code "41") (name "unconnected-(U5-Pad4)") (class "Default")
      (node (ref "U5") (pin "4") (pinfunction "4_4") (pintype "passive"))
    )
  )
)
